# ccr_v10.net
KiCad netlist of a schematic drawn in EAGLE
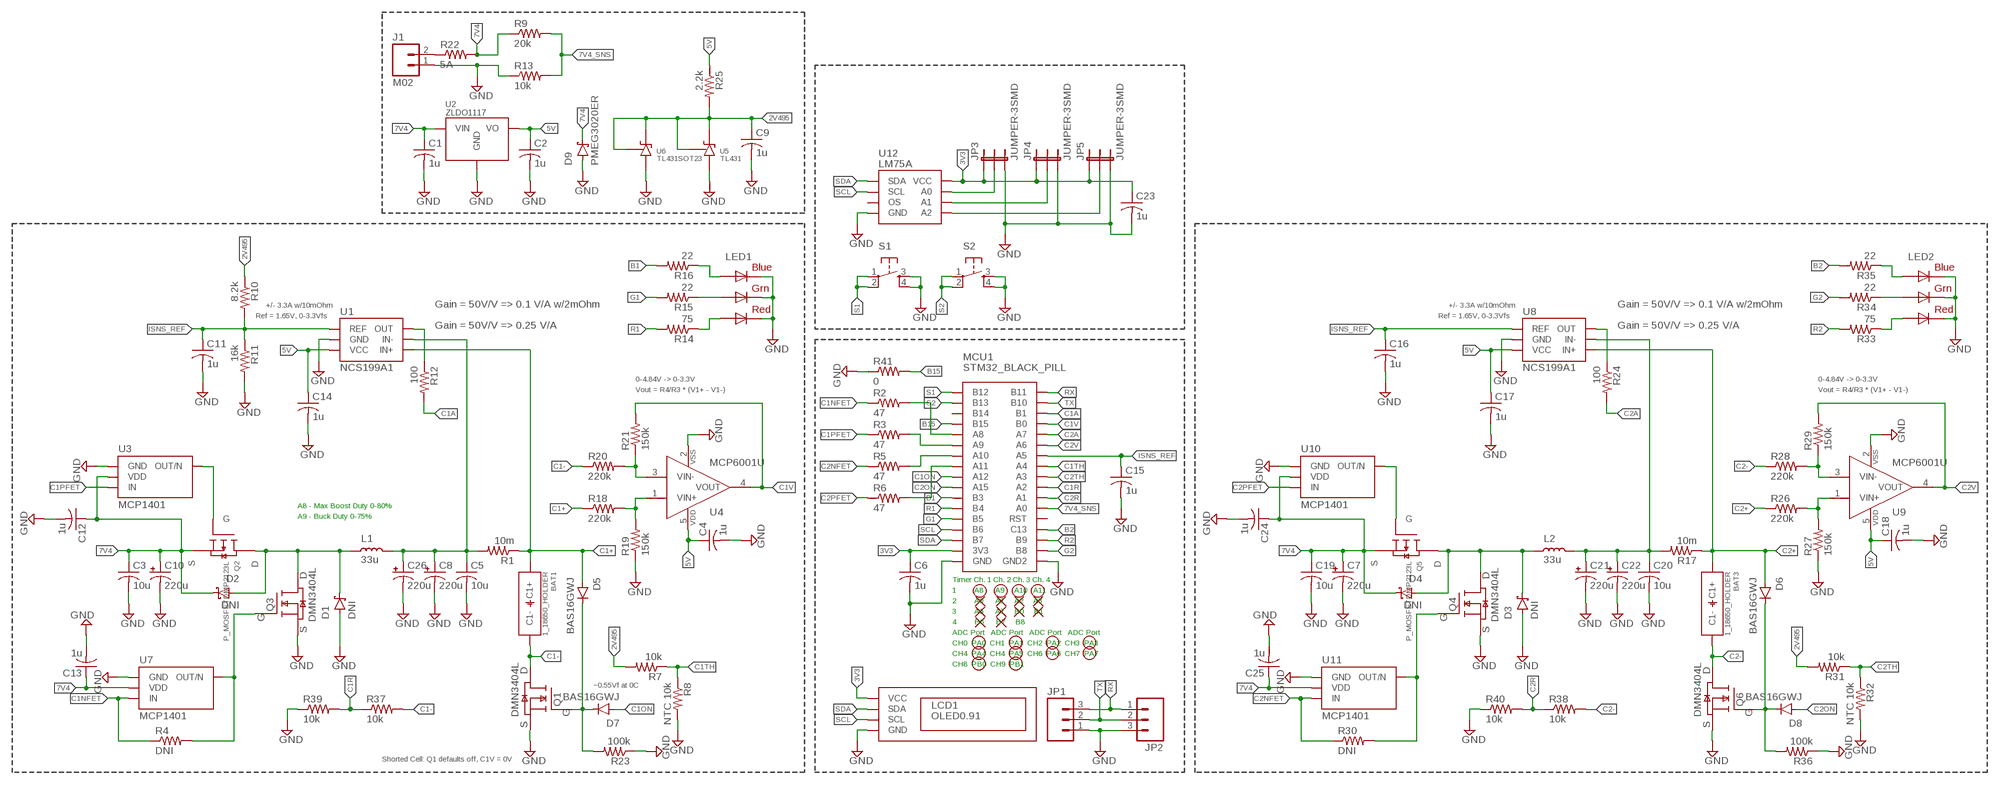
[diagram p0: schematic, sheet 1]

(export (version "E")
  (design (tool "Eeschema 10.0.6"))
  (components
    (comp (ref "BAT1")
      (value "1_18650_HOLDER")
      (footprint "eagle-import:1S_18650_SMD_NH")
      (libsource (lib "eagle-import") (part "1_18650_HOLDER"))
    )
    (comp (ref "BAT3")
      (value "1_18650_HOLDER")
      (footprint "eagle-import:1S_18650_SMD_NH")
      (libsource (lib "eagle-import") (part "1_18650_HOLDER"))
    )
    (comp (ref "C1")
      (value "1u")
      (footprint "eagle-import:C0402")
      (libsource (lib "eagle-import") (part "C-USC0402"))
    )
    (comp (ref "C2")
      (value "1u")
      (footprint "eagle-import:C0402")
      (libsource (lib "eagle-import") (part "C-USC0402"))
    )
    (comp (ref "C3")
      (value "10u")
      (footprint "eagle-import:C1206")
      (libsource (lib "eagle-import") (part "C-USC1206"))
    )
    (comp (ref "C4")
      (value "1u")
      (footprint "eagle-import:C0402")
      (libsource (lib "eagle-import") (part "C-USC0402"))
    )
    (comp (ref "C5")
      (value "10u")
      (footprint "eagle-import:C1206")
      (libsource (lib "eagle-import") (part "C-USC1206"))
    )
    (comp (ref "C6")
      (value "1u")
      (footprint "eagle-import:C0402")
      (libsource (lib "eagle-import") (part "C-USC0402"))
    )
    (comp (ref "C7")
      (value "220u")
      (footprint "eagle-import:PANASONIC_D")
      (libsource (lib "eagle-import") (part "CPOL-USD"))
    )
    (comp (ref "C8")
      (value "220u")
      (footprint "eagle-import:PANASONIC_D")
      (libsource (lib "eagle-import") (part "CPOL-USD"))
    )
    (comp (ref "C9")
      (value "1u")
      (footprint "eagle-import:C0402")
      (libsource (lib "eagle-import") (part "C-USC0402"))
    )
    (comp (ref "C10")
      (value "220u")
      (footprint "eagle-import:PANASONIC_D")
      (libsource (lib "eagle-import") (part "CPOL-USD"))
    )
    (comp (ref "C11")
      (value "1u")
      (footprint "eagle-import:C0402")
      (libsource (lib "eagle-import") (part "C-USC0402"))
    )
    (comp (ref "C12")
      (value "1u")
      (footprint "eagle-import:C0402")
      (libsource (lib "eagle-import") (part "C-USC0402"))
    )
    (comp (ref "C13")
      (value "1u")
      (footprint "eagle-import:C0402")
      (libsource (lib "eagle-import") (part "C-USC0402"))
    )
    (comp (ref "C14")
      (value "1u")
      (footprint "eagle-import:C0402")
      (libsource (lib "eagle-import") (part "C-USC0402"))
    )
    (comp (ref "C15")
      (value "1u")
      (footprint "eagle-import:C0402")
      (libsource (lib "eagle-import") (part "C-USC0402"))
    )
    (comp (ref "C16")
      (value "1u")
      (footprint "eagle-import:C0402")
      (libsource (lib "eagle-import") (part "C-USC0402"))
    )
    (comp (ref "C17")
      (value "1u")
      (footprint "eagle-import:C0402")
      (libsource (lib "eagle-import") (part "C-USC0402"))
    )
    (comp (ref "C18")
      (value "1u")
      (footprint "eagle-import:C0402")
      (libsource (lib "eagle-import") (part "C-USC0402"))
    )
    (comp (ref "C19")
      (value "10u")
      (footprint "eagle-import:C1206")
      (libsource (lib "eagle-import") (part "C-USC1206"))
    )
    (comp (ref "C20")
      (value "10u")
      (footprint "eagle-import:C1206")
      (libsource (lib "eagle-import") (part "C-USC1206"))
    )
    (comp (ref "C21")
      (value "220u")
      (footprint "eagle-import:PANASONIC_D")
      (libsource (lib "eagle-import") (part "CPOL-USD"))
    )
    (comp (ref "C22")
      (value "220u")
      (footprint "eagle-import:PANASONIC_D")
      (libsource (lib "eagle-import") (part "CPOL-USD"))
    )
    (comp (ref "C23")
      (value "1u")
      (footprint "eagle-import:C0402")
      (libsource (lib "eagle-import") (part "C-USC0402"))
    )
    (comp (ref "C24")
      (value "1u")
      (footprint "eagle-import:C0402")
      (libsource (lib "eagle-import") (part "C-USC0402"))
    )
    (comp (ref "C25")
      (value "1u")
      (footprint "eagle-import:C0402")
      (libsource (lib "eagle-import") (part "C-USC0402"))
    )
    (comp (ref "C26")
      (value "220u")
      (footprint "eagle-import:PANASONIC_D")
      (libsource (lib "eagle-import") (part "CPOL-USD"))
    )
    (comp (ref "D1")
      (value "DNI")
      (footprint "eagle-import:SOD123W")
      (libsource (lib "eagle-import") (part "PMEG3020ER"))
    )
    (comp (ref "D2")
      (value "DNI")
      (footprint "eagle-import:SOD123W")
      (libsource (lib "eagle-import") (part "PMEG3020ER"))
    )
    (comp (ref "D3")
      (value "DNI")
      (footprint "eagle-import:SOD123W")
      (libsource (lib "eagle-import") (part "PMEG3020ER"))
    )
    (comp (ref "D4")
      (value "DNI")
      (footprint "eagle-import:SOD123W")
      (libsource (lib "eagle-import") (part "PMEG3020ER"))
    )
    (comp (ref "D5")
      (value "BAS16GWJ")
      (footprint "eagle-import:SOD323")
      (libsource (lib "eagle-import") (part "BAT60A"))
    )
    (comp (ref "D6")
      (value "BAS16GWJ")
      (footprint "eagle-import:SOD323")
      (libsource (lib "eagle-import") (part "BAT60A"))
    )
    (comp (ref "D7")
      (value "BAS16GWJ")
      (footprint "eagle-import:SOD323")
      (libsource (lib "eagle-import") (part "BAT60A"))
    )
    (comp (ref "D8")
      (value "BAS16GWJ")
      (footprint "eagle-import:SOD323")
      (libsource (lib "eagle-import") (part "BAT60A"))
    )
    (comp (ref "D9")
      (value "PMEG3020ER")
      (footprint "eagle-import:SOD123W")
      (libsource (lib "eagle-import") (part "PMEG3020ER"))
    )
    (comp (ref "J1")
      (value "M02")
      (footprint "eagle-import:PHOENIXCONTACT1935161")
      (libsource (lib "eagle-import") (part "M02"))
    )
    (comp (ref "JP1")
      (value "M03PTH")
      (footprint "eagle-import:1X03")
      (libsource (lib "eagle-import") (part "M03PTH"))
    )
    (comp (ref "JP2")
      (value "M03PTH")
      (footprint "eagle-import:1X03")
      (libsource (lib "eagle-import") (part "M03PTH"))
    )
    (comp (ref "JP3")
      (value "JUMPER-3SMD")
      (footprint "eagle-import:SJ_3")
      (libsource (lib "eagle-import") (part "JUMPER-3SMD"))
    )
    (comp (ref "JP4")
      (value "JUMPER-3SMD")
      (footprint "eagle-import:SJ_3")
      (libsource (lib "eagle-import") (part "JUMPER-3SMD"))
    )
    (comp (ref "JP5")
      (value "JUMPER-3SMD")
      (footprint "eagle-import:SJ_3")
      (libsource (lib "eagle-import") (part "JUMPER-3SMD"))
    )
    (comp (ref "L1")
      (value "33u")
      (footprint "eagle-import:INDUCTOR_SMD_13MM")
      (libsource (lib "eagle-import") (part "SDR1307"))
    )
    (comp (ref "L2")
      (value "33u")
      (footprint "eagle-import:INDUCTOR_SMD_13MM")
      (libsource (lib "eagle-import") (part "SDR1307"))
    )
    (comp (ref "LCD1")
      (value "OLED0.91")
      (footprint "eagle-import:OLED0.91")
      (libsource (lib "eagle-import") (part "OLED0.91"))
    )
    (comp (ref "LED1")
      (value "RGBLED5050")
      (footprint "eagle-import:RGBLED5050")
      (libsource (lib "eagle-import") (part "RGBLED5050"))
    )
    (comp (ref "LED2")
      (value "RGBLED5050")
      (footprint "eagle-import:RGBLED5050")
      (libsource (lib "eagle-import") (part "RGBLED5050"))
    )
    (comp (ref "MCU1")
      (value "STM32_BLACK_PILL")
      (footprint "eagle-import:STM32_BLACK_PILL_BOT")
      (libsource (lib "eagle-import") (part "STM32_BLACK_PILL"))
    )
    (comp (ref "Q1")
      (value "DMN3404L")
      (footprint "eagle-import:SOT23")
      (libsource (lib "eagle-import") (part "DMN3404L"))
    )
    (comp (ref "Q2")
      (value "P_MOSFETDMP2123L")
      (footprint "eagle-import:SOT23")
      (libsource (lib "eagle-import") (part "P_MOSFETDMP2123L"))
    )
    (comp (ref "Q3")
      (value "DMN3404L")
      (footprint "eagle-import:SOT23")
      (libsource (lib "eagle-import") (part "DMN3404L"))
    )
    (comp (ref "Q4")
      (value "DMN3404L")
      (footprint "eagle-import:SOT23")
      (libsource (lib "eagle-import") (part "DMN3404L"))
    )
    (comp (ref "Q5")
      (value "P_MOSFETDMP2123L")
      (footprint "eagle-import:SOT23")
      (libsource (lib "eagle-import") (part "P_MOSFETDMP2123L"))
    )
    (comp (ref "Q6")
      (value "DMN3404L")
      (footprint "eagle-import:SOT23")
      (libsource (lib "eagle-import") (part "DMN3404L"))
    )
    (comp (ref "R1")
      (value "10m")
      (footprint "eagle-import:R2512")
      (libsource (lib "eagle-import") (part "R-US_R2512"))
    )
    (comp (ref "R2")
      (value "47")
      (footprint "eagle-import:R0402")
      (libsource (lib "eagle-import") (part "R-US_R0402"))
    )
    (comp (ref "R3")
      (value "47")
      (footprint "eagle-import:R0402")
      (libsource (lib "eagle-import") (part "R-US_R0402"))
    )
    (comp (ref "R4")
      (value "DNI")
      (footprint "eagle-import:R0402")
      (libsource (lib "eagle-import") (part "R-US_R0402"))
    )
    (comp (ref "R5")
      (value "47")
      (footprint "eagle-import:R0402")
      (libsource (lib "eagle-import") (part "R-US_R0402"))
    )
    (comp (ref "R6")
      (value "47")
      (footprint "eagle-import:R0402")
      (libsource (lib "eagle-import") (part "R-US_R0402"))
    )
    (comp (ref "R7")
      (value "10k")
      (footprint "eagle-import:R0402")
      (libsource (lib "eagle-import") (part "R-US_R0402"))
    )
    (comp (ref "R8")
      (value "NTC 10k")
      (footprint "eagle-import:R0402")
      (libsource (lib "eagle-import") (part "R-US_R0402"))
    )
    (comp (ref "R9")
      (value "20k")
      (footprint "eagle-import:R0402")
      (libsource (lib "eagle-import") (part "R-US_R0402"))
    )
    (comp (ref "R10")
      (value "8.2k")
      (footprint "eagle-import:R0402")
      (libsource (lib "eagle-import") (part "R-US_R0402"))
    )
    (comp (ref "R11")
      (value "16k")
      (footprint "eagle-import:R0402")
      (libsource (lib "eagle-import") (part "R-US_R0402"))
    )
    (comp (ref "R12")
      (value "100")
      (footprint "eagle-import:R0402")
      (libsource (lib "eagle-import") (part "R-US_R0402"))
    )
    (comp (ref "R13")
      (value "10k")
      (footprint "eagle-import:R0402")
      (libsource (lib "eagle-import") (part "R-US_R0402"))
    )
    (comp (ref "R14")
      (value "75")
      (footprint "eagle-import:R0402")
      (libsource (lib "eagle-import") (part "R-US_R0402"))
    )
    (comp (ref "R15")
      (value "22")
      (footprint "eagle-import:R0402")
      (libsource (lib "eagle-import") (part "R-US_R0402"))
    )
    (comp (ref "R16")
      (value "22")
      (footprint "eagle-import:R0402")
      (libsource (lib "eagle-import") (part "R-US_R0402"))
    )
    (comp (ref "R17")
      (value "10m")
      (footprint "eagle-import:R2512")
      (libsource (lib "eagle-import") (part "R-US_R2512"))
    )
    (comp (ref "R18")
      (value "220k")
      (footprint "eagle-import:R0402")
      (libsource (lib "eagle-import") (part "R-US_R0402"))
    )
    (comp (ref "R19")
      (value "150k")
      (footprint "eagle-import:R0402")
      (libsource (lib "eagle-import") (part "R-US_R0402"))
    )
    (comp (ref "R20")
      (value "220k")
      (footprint "eagle-import:R0402")
      (libsource (lib "eagle-import") (part "R-US_R0402"))
    )
    (comp (ref "R21")
      (value "150k")
      (footprint "eagle-import:R0402")
      (libsource (lib "eagle-import") (part "R-US_R0402"))
    )
    (comp (ref "R22")
      (value "5A")
      (footprint "eagle-import:R1206")
      (libsource (lib "eagle-import") (part "R-US_R1206"))
    )
    (comp (ref "R23")
      (value "100k")
      (footprint "eagle-import:R0402")
      (libsource (lib "eagle-import") (part "R-US_R0402"))
    )
    (comp (ref "R24")
      (value "100")
      (footprint "eagle-import:R0402")
      (libsource (lib "eagle-import") (part "R-US_R0402"))
    )
    (comp (ref "R25")
      (value "2.2k")
      (footprint "eagle-import:R0402")
      (libsource (lib "eagle-import") (part "R-US_R0402"))
    )
    (comp (ref "R26")
      (value "220k")
      (footprint "eagle-import:R0402")
      (libsource (lib "eagle-import") (part "R-US_R0402"))
    )
    (comp (ref "R27")
      (value "150k")
      (footprint "eagle-import:R0402")
      (libsource (lib "eagle-import") (part "R-US_R0402"))
    )
    (comp (ref "R28")
      (value "220k")
      (footprint "eagle-import:R0402")
      (libsource (lib "eagle-import") (part "R-US_R0402"))
    )
    (comp (ref "R29")
      (value "150k")
      (footprint "eagle-import:R0402")
      (libsource (lib "eagle-import") (part "R-US_R0402"))
    )
    (comp (ref "R30")
      (value "DNI")
      (footprint "eagle-import:R0402")
      (libsource (lib "eagle-import") (part "R-US_R0402"))
    )
    (comp (ref "R31")
      (value "10k")
      (footprint "eagle-import:R0402")
      (libsource (lib "eagle-import") (part "R-US_R0402"))
    )
    (comp (ref "R32")
      (value "NTC 10k")
      (footprint "eagle-import:R0402")
      (libsource (lib "eagle-import") (part "R-US_R0402"))
    )
    (comp (ref "R33")
      (value "75")
      (footprint "eagle-import:R0402")
      (libsource (lib "eagle-import") (part "R-US_R0402"))
    )
    (comp (ref "R34")
      (value "22")
      (footprint "eagle-import:R0402")
      (libsource (lib "eagle-import") (part "R-US_R0402"))
    )
    (comp (ref "R35")
      (value "22")
      (footprint "eagle-import:R0402")
      (libsource (lib "eagle-import") (part "R-US_R0402"))
    )
    (comp (ref "R36")
      (value "100k")
      (footprint "eagle-import:R0402")
      (libsource (lib "eagle-import") (part "R-US_R0402"))
    )
    (comp (ref "R37")
      (value "10k")
      (footprint "eagle-import:R0402")
      (libsource (lib "eagle-import") (part "R-US_R0402"))
    )
    (comp (ref "R38")
      (value "10k")
      (footprint "eagle-import:R0402")
      (libsource (lib "eagle-import") (part "R-US_R0402"))
    )
    (comp (ref "R39")
      (value "10k")
      (footprint "eagle-import:R0402")
      (libsource (lib "eagle-import") (part "R-US_R0402"))
    )
    (comp (ref "R40")
      (value "10k")
      (footprint "eagle-import:R0402")
      (libsource (lib "eagle-import") (part "R-US_R0402"))
    )
    (comp (ref "R41")
      (value "0")
      (footprint "eagle-import:R0402")
      (libsource (lib "eagle-import") (part "R-US_R0402"))
    )
    (comp (ref "S1")
      (value "TAC_SWITCHSMD")
      (footprint "eagle-import:TACTILE_SWITCH_SMD")
      (libsource (lib "eagle-import") (part "TAC_SWITCHSMD"))
    )
    (comp (ref "S2")
      (value "TAC_SWITCHSMD")
      (footprint "eagle-import:TACTILE_SWITCH_SMD")
      (libsource (lib "eagle-import") (part "TAC_SWITCHSMD"))
    )
    (comp (ref "U1")
      (value "NCS199A1")
      (footprint "eagle-import:SOT-363")
      (libsource (lib "eagle-import") (part "INA214"))
    )
    (comp (ref "U2")
      (value "ZLDO1117")
      (footprint "eagle-import:TO-261")
      (libsource (lib "eagle-import") (part "ZLDO1117"))
    )
    (comp (ref "U3")
      (value "MCP1401")
      (footprint "eagle-import:SOT23-5")
      (libsource (lib "eagle-import") (part "MCP1401"))
    )
    (comp (ref "U4")
      (value "MCP6001U")
      (footprint "eagle-import:SOT23-5")
      (libsource (lib "eagle-import") (part "MCP6001U"))
    )
    (comp (ref "U5")
      (value "TL431")
      (footprint "eagle-import:SOT23-5")
      (libsource (lib "eagle-import") (part "TL431"))
    )
    (comp (ref "U6")
      (value "TL431SOT23")
      (footprint "eagle-import:SOT23")
      (libsource (lib "eagle-import") (part "TL431SOT23"))
    )
    (comp (ref "U7")
      (value "MCP1401")
      (footprint "eagle-import:SOT23-5")
      (libsource (lib "eagle-import") (part "MCP1401"))
    )
    (comp (ref "U8")
      (value "NCS199A1")
      (footprint "eagle-import:SOT-363")
      (libsource (lib "eagle-import") (part "INA214"))
    )
    (comp (ref "U9")
      (value "MCP6001U")
      (footprint "eagle-import:SOT23-5")
      (libsource (lib "eagle-import") (part "MCP6001U"))
    )
    (comp (ref "U10")
      (value "MCP1401")
      (footprint "eagle-import:SOT23-5")
      (libsource (lib "eagle-import") (part "MCP1401"))
    )
    (comp (ref "U11")
      (value "MCP1401")
      (footprint "eagle-import:SOT23-5")
      (libsource (lib "eagle-import") (part "MCP1401"))
    )
    (comp (ref "U12")
      (value "LM75A")
      (footprint "eagle-import:8-SOIC")
      (libsource (lib "eagle-import") (part "LM75A"))
    )
  )
  (nets
    (net (code "1") (name "2V495") (class "Default")
      (node (ref "C9") (pin "1") (pinfunction "1_1") (pintype "passive"))
      (node (ref "R10") (pin "1") (pinfunction "1_1") (pintype "passive"))
      (node (ref "R25") (pin "2") (pinfunction "2_2") (pintype "passive"))
      (node (ref "R31") (pin "2") (pinfunction "2_2") (pintype "passive"))
      (node (ref "R7") (pin "2") (pinfunction "2_2") (pintype "passive"))
      (node (ref "U5") (pin "3") (pinfunction "K_3") (pintype "passive"))
      (node (ref "U5") (pin "4") (pinfunction "REF_4") (pintype "passive"))
      (node (ref "U6") (pin "1") (pinfunction "K_1") (pintype "passive"))
      (node (ref "U6") (pin "2") (pinfunction "REF_2") (pintype "passive"))
    )
    (net (code "2") (name "3V3") (class "Default")
      (node (ref "C23") (pin "1") (pinfunction "1_1") (pintype "passive"))
      (node (ref "C6") (pin "1") (pinfunction "1_1") (pintype "passive"))
      (node (ref "JP3") (pin "1") (pinfunction "1_1") (pintype "passive"))
      (node (ref "JP4") (pin "1") (pinfunction "1_1") (pintype "passive"))
      (node (ref "JP5") (pin "1") (pinfunction "1_1") (pintype "passive"))
      (node (ref "LCD1") (pin "2-VCC") (pinfunction "VCC_2-VCC") (pintype "bidirectional"))
      (node (ref "MCU1") (pin "3V3") (pinfunction "3V3_3V3") (pintype "bidirectional"))
      (node (ref "U12") (pin "8") (pinfunction "VCC_8") (pintype "bidirectional"))
    )
    (net (code "3") (name "5V") (class "Default")
      (node (ref "C14") (pin "1") (pinfunction "1_1") (pintype "passive"))
      (node (ref "C17") (pin "1") (pinfunction "1_1") (pintype "passive"))
      (node (ref "C18") (pin "1") (pinfunction "1_1") (pintype "passive"))
      (node (ref "C2") (pin "1") (pinfunction "1_1") (pintype "passive"))
      (node (ref "C4") (pin "1") (pinfunction "1_1") (pintype "passive"))
      (node (ref "R25") (pin "1") (pinfunction "1_1") (pintype "passive"))
      (node (ref "U1") (pin "3") (pinfunction "VCC_3") (pintype "bidirectional"))
      (node (ref "U2") (pin "2") (pinfunction "VO_2") (pintype "bidirectional"))
      (node (ref "U2") (pin "4") (pinfunction "VO_4") (pintype "bidirectional"))
      (node (ref "U4") (pin "5") (pinfunction "VDD_5") (pintype "bidirectional"))
      (node (ref "U8") (pin "3") (pinfunction "VCC_3") (pintype "bidirectional"))
      (node (ref "U9") (pin "5") (pinfunction "VDD_5") (pintype "bidirectional"))
    )
    (net (code "4") (name "7V4") (class "Default")
      (node (ref "C1") (pin "1") (pinfunction "1_1") (pintype "passive"))
      (node (ref "C10") (pin "+") (pinfunction "+_+") (pintype "passive"))
      (node (ref "C12") (pin "1") (pinfunction "1_1") (pintype "passive"))
      (node (ref "C13") (pin "1") (pinfunction "1_1") (pintype "passive"))
      (node (ref "C19") (pin "1") (pinfunction "1_1") (pintype "passive"))
      (node (ref "C24") (pin "1") (pinfunction "1_1") (pintype "passive"))
      (node (ref "C25") (pin "1") (pinfunction "1_1") (pintype "passive"))
      (node (ref "C3") (pin "1") (pinfunction "1_1") (pintype "passive"))
      (node (ref "C7") (pin "+") (pinfunction "+_+") (pintype "passive"))
      (node (ref "D2") (pin "K") (pinfunction "CATHODE_K") (pintype "passive"))
      (node (ref "D4") (pin "K") (pinfunction "CATHODE_K") (pintype "passive"))
      (node (ref "D9") (pin "K") (pinfunction "CATHODE_K") (pintype "passive"))
      (node (ref "Q2") (pin "2") (pinfunction "S_2") (pintype "bidirectional"))
      (node (ref "Q5") (pin "2") (pinfunction "S_2") (pintype "bidirectional"))
      (node (ref "R22") (pin "2") (pinfunction "2_2") (pintype "passive"))
      (node (ref "R9") (pin "1") (pinfunction "1_1") (pintype "passive"))
      (node (ref "U10") (pin "2") (pinfunction "VDD_2") (pintype "bidirectional"))
      (node (ref "U11") (pin "2") (pinfunction "VDD_2") (pintype "bidirectional"))
      (node (ref "U2") (pin "3") (pinfunction "VIN_3") (pintype "bidirectional"))
      (node (ref "U3") (pin "2") (pinfunction "VDD_2") (pintype "bidirectional"))
      (node (ref "U7") (pin "2") (pinfunction "VDD_2") (pintype "bidirectional"))
    )
    (net (code "5") (name "7V4_SNS") (class "Default")
      (node (ref "MCU1") (pin "A0") (pinfunction "A0_A0") (pintype "bidirectional"))
      (node (ref "R13") (pin "2") (pinfunction "2_2") (pintype "passive"))
      (node (ref "R9") (pin "2") (pinfunction "2_2") (pintype "passive"))
    )
    (net (code "6") (name "B1") (class "Default")
      (node (ref "MCU1") (pin "B3") (pinfunction "B3_B3") (pintype "bidirectional"))
      (node (ref "R16") (pin "2") (pinfunction "2_2") (pintype "passive"))
    )
    (net (code "7") (name "B2") (class "Default")
      (node (ref "MCU1") (pin "C13") (pinfunction "C13_C13") (pintype "bidirectional"))
      (node (ref "R35") (pin "2") (pinfunction "2_2") (pintype "passive"))
    )
    (net (code "8") (name "B15") (class "Default")
      (node (ref "MCU1") (pin "B15") (pinfunction "B15_B15") (pintype "bidirectional"))
      (node (ref "R41") (pin "2") (pinfunction "2_2") (pintype "passive"))
    )
    (net (code "9") (name "C1+") (class "Default")
      (node (ref "BAT1") (pin "1+") (pinfunction "C1+_1+") (pintype "bidirectional"))
      (node (ref "D5") (pin "A") (pinfunction "ANODE_A") (pintype "passive"))
      (node (ref "R1") (pin "1") (pinfunction "1_1") (pintype "passive"))
      (node (ref "R18") (pin "1") (pinfunction "1_1") (pintype "passive"))
      (node (ref "U1") (pin "4") (pinfunction "IN+_4") (pintype "bidirectional"))
    )
    (net (code "10") (name "C1-") (class "Default")
      (node (ref "BAT1") (pin "1-") (pinfunction "C1-_1-") (pintype "bidirectional"))
      (node (ref "Q1") (pin "3") (pinfunction "D_3") (pintype "passive"))
      (node (ref "R20") (pin "1") (pinfunction "1_1") (pintype "passive"))
      (node (ref "R37") (pin "2") (pinfunction "2_2") (pintype "passive"))
    )
    (net (code "11") (name "C1A") (class "Default")
      (node (ref "MCU1") (pin "B1") (pinfunction "B1_B1") (pintype "bidirectional"))
      (node (ref "R12") (pin "2") (pinfunction "2_2") (pintype "passive"))
    )
    (net (code "12") (name "C1NFET") (class "Default")
      (node (ref "R2") (pin "1") (pinfunction "1_1") (pintype "passive"))
      (node (ref "R4") (pin "1") (pinfunction "1_1") (pintype "passive"))
      (node (ref "U7") (pin "3") (pinfunction "IN_3") (pintype "bidirectional"))
    )
    (net (code "13") (name "C1ON") (class "Default")
      (node (ref "D7") (pin "A") (pinfunction "ANODE_A") (pintype "passive"))
      (node (ref "MCU1") (pin "A12") (pinfunction "A12_A12") (pintype "bidirectional"))
    )
    (net (code "14") (name "C1PFET") (class "Default")
      (node (ref "R3") (pin "1") (pinfunction "1_1") (pintype "passive"))
      (node (ref "U3") (pin "3") (pinfunction "IN_3") (pintype "bidirectional"))
    )
    (net (code "15") (name "C1R") (class "Default")
      (node (ref "MCU1") (pin "A2") (pinfunction "A2_A2") (pintype "bidirectional"))
      (node (ref "R37") (pin "1") (pinfunction "1_1") (pintype "passive"))
      (node (ref "R39") (pin "2") (pinfunction "2_2") (pintype "passive"))
    )
    (net (code "16") (name "C1TH") (class "Default")
      (node (ref "MCU1") (pin "A4") (pinfunction "A4_A4") (pintype "bidirectional"))
      (node (ref "R7") (pin "1") (pinfunction "1_1") (pintype "passive"))
      (node (ref "R8") (pin "1") (pinfunction "1_1") (pintype "passive"))
    )
    (net (code "17") (name "C1V") (class "Default")
      (node (ref "MCU1") (pin "B0") (pinfunction "B0_B0") (pintype "bidirectional"))
      (node (ref "R21") (pin "2") (pinfunction "2_2") (pintype "passive"))
      (node (ref "U4") (pin "4") (pinfunction "VOUT_4") (pintype "bidirectional"))
    )
    (net (code "18") (name "C2+") (class "Default")
      (node (ref "BAT3") (pin "1+") (pinfunction "C1+_1+") (pintype "bidirectional"))
      (node (ref "D6") (pin "A") (pinfunction "ANODE_A") (pintype "passive"))
      (node (ref "R17") (pin "1") (pinfunction "1_1") (pintype "passive"))
      (node (ref "R26") (pin "1") (pinfunction "1_1") (pintype "passive"))
      (node (ref "U8") (pin "4") (pinfunction "IN+_4") (pintype "bidirectional"))
    )
    (net (code "19") (name "C2-") (class "Default")
      (node (ref "BAT3") (pin "1-") (pinfunction "C1-_1-") (pintype "bidirectional"))
      (node (ref "Q6") (pin "3") (pinfunction "D_3") (pintype "passive"))
      (node (ref "R28") (pin "1") (pinfunction "1_1") (pintype "passive"))
      (node (ref "R38") (pin "2") (pinfunction "2_2") (pintype "passive"))
    )
    (net (code "20") (name "C2A") (class "Default")
      (node (ref "MCU1") (pin "A7") (pinfunction "A7_A7") (pintype "bidirectional"))
      (node (ref "R24") (pin "2") (pinfunction "2_2") (pintype "passive"))
    )
    (net (code "21") (name "C2NFET") (class "Default")
      (node (ref "R30") (pin "1") (pinfunction "1_1") (pintype "passive"))
      (node (ref "R5") (pin "1") (pinfunction "1_1") (pintype "passive"))
      (node (ref "U11") (pin "3") (pinfunction "IN_3") (pintype "bidirectional"))
    )
    (net (code "22") (name "C2ON") (class "Default")
      (node (ref "D8") (pin "A") (pinfunction "ANODE_A") (pintype "passive"))
      (node (ref "MCU1") (pin "A15") (pinfunction "A15_A15") (pintype "bidirectional"))
    )
    (net (code "23") (name "C2PFET") (class "Default")
      (node (ref "R6") (pin "1") (pinfunction "1_1") (pintype "passive"))
      (node (ref "U10") (pin "3") (pinfunction "IN_3") (pintype "bidirectional"))
    )
    (net (code "24") (name "C2R") (class "Default")
      (node (ref "MCU1") (pin "A1") (pinfunction "A1_A1") (pintype "bidirectional"))
      (node (ref "R38") (pin "1") (pinfunction "1_1") (pintype "passive"))
      (node (ref "R40") (pin "2") (pinfunction "2_2") (pintype "passive"))
    )
    (net (code "25") (name "C2TH") (class "Default")
      (node (ref "MCU1") (pin "A3") (pinfunction "A3_A3") (pintype "bidirectional"))
      (node (ref "R31") (pin "1") (pinfunction "1_1") (pintype "passive"))
      (node (ref "R32") (pin "1") (pinfunction "1_1") (pintype "passive"))
    )
    (net (code "26") (name "C2V") (class "Default")
      (node (ref "MCU1") (pin "A6") (pinfunction "A6_A6") (pintype "bidirectional"))
      (node (ref "R29") (pin "2") (pinfunction "2_2") (pintype "passive"))
      (node (ref "U9") (pin "4") (pinfunction "VOUT_4") (pintype "bidirectional"))
    )
    (net (code "27") (name "G1") (class "Default")
      (node (ref "MCU1") (pin "B5") (pinfunction "B5_B5") (pintype "bidirectional"))
      (node (ref "R15") (pin "2") (pinfunction "2_2") (pintype "passive"))
    )
    (net (code "28") (name "G2") (class "Default")
      (node (ref "MCU1") (pin "B8") (pinfunction "B8_B8") (pintype "bidirectional"))
      (node (ref "R34") (pin "2") (pinfunction "2_2") (pintype "passive"))
    )
    (net (code "29") (name "GND") (class "Default")
      (node (ref "C1") (pin "2") (pinfunction "2_2") (pintype "passive"))
      (node (ref "C10") (pin "-") (pinfunction "-_-") (pintype "passive"))
      (node (ref "C11") (pin "2") (pinfunction "2_2") (pintype "passive"))
      (node (ref "C12") (pin "2") (pinfunction "2_2") (pintype "passive"))
      (node (ref "C13") (pin "2") (pinfunction "2_2") (pintype "passive"))
      (node (ref "C14") (pin "2") (pinfunction "2_2") (pintype "passive"))
      (node (ref "C15") (pin "2") (pinfunction "2_2") (pintype "passive"))
      (node (ref "C16") (pin "2") (pinfunction "2_2") (pintype "passive"))
      (node (ref "C17") (pin "2") (pinfunction "2_2") (pintype "passive"))
      (node (ref "C18") (pin "2") (pinfunction "2_2") (pintype "passive"))
      (node (ref "C19") (pin "2") (pinfunction "2_2") (pintype "passive"))
      (node (ref "C2") (pin "2") (pinfunction "2_2") (pintype "passive"))
      (node (ref "C20") (pin "2") (pinfunction "2_2") (pintype "passive"))
      (node (ref "C21") (pin "-") (pinfunction "-_-") (pintype "passive"))
      (node (ref "C22") (pin "-") (pinfunction "-_-") (pintype "passive"))
      (node (ref "C23") (pin "2") (pinfunction "2_2") (pintype "passive"))
      (node (ref "C24") (pin "2") (pinfunction "2_2") (pintype "passive"))
      (node (ref "C25") (pin "2") (pinfunction "2_2") (pintype "passive"))
      (node (ref "C26") (pin "-") (pinfunction "-_-") (pintype "passive"))
      (node (ref "C3") (pin "2") (pinfunction "2_2") (pintype "passive"))
      (node (ref "C4") (pin "2") (pinfunction "2_2") (pintype "passive"))
      (node (ref "C5") (pin "2") (pinfunction "2_2") (pintype "passive"))
      (node (ref "C6") (pin "2") (pinfunction "2_2") (pintype "passive"))
      (node (ref "C7") (pin "-") (pinfunction "-_-") (pintype "passive"))
      (node (ref "C8") (pin "-") (pinfunction "-_-") (pintype "passive"))
      (node (ref "C9") (pin "2") (pinfunction "2_2") (pintype "passive"))
      (node (ref "D1") (pin "A") (pinfunction "ANODE_A") (pintype "passive"))
      (node (ref "D3") (pin "A") (pinfunction "ANODE_A") (pintype "passive"))
      (node (ref "D9") (pin "A") (pinfunction "ANODE_A") (pintype "passive"))
      (node (ref "J1") (pin "1") (pinfunction "1_1") (pintype "passive"))
      (node (ref "JP1") (pin "1") (pinfunction "1_1") (pintype "passive"))
      (node (ref "JP2") (pin "3") (pinfunction "3_3") (pintype "passive"))
      (node (ref "JP3") (pin "3") (pinfunction "3_3") (pintype "passive"))
      (node (ref "JP4") (pin "3") (pinfunction "3_3") (pintype "passive"))
      (node (ref "JP5") (pin "3") (pinfunction "3_3") (pintype "passive"))
      (node (ref "LCD1") (pin "1=GND") (pinfunction "GND_1=GND") (pintype "bidirectional"))
      (node (ref "LED1") (pin "4") (pinfunction "BLUE_C_4") (pintype "bidirectional"))
      (node (ref "LED1") (pin "5") (pinfunction "RED_C_5") (pintype "bidirectional"))
      (node (ref "LED1") (pin "6") (pinfunction "GREEN_C_6") (pintype "bidirectional"))
      (node (ref "LED2") (pin "4") (pinfunction "BLUE_C_4") (pintype "bidirectional"))
      (node (ref "LED2") (pin "5") (pinfunction "RED_C_5") (pintype "bidirectional"))
      (node (ref "LED2") (pin "6") (pinfunction "GREEN_C_6") (pintype "bidirectional"))
      (node (ref "MCU1") (pin "GND1") (pinfunction "GND_GND1") (pintype "bidirectional"))
      (node (ref "MCU1") (pin "GND2") (pinfunction "GND2_GND2") (pintype "bidirectional"))
      (node (ref "Q1") (pin "2") (pinfunction "S_2") (pintype "passive"))
      (node (ref "Q3") (pin "2") (pinfunction "S_2") (pintype "passive"))
      (node (ref "Q4") (pin "2") (pinfunction "S_2") (pintype "passive"))
      (node (ref "Q6") (pin "2") (pinfunction "S_2") (pintype "passive"))
      (node (ref "R11") (pin "2") (pinfunction "2_2") (pintype "passive"))
      (node (ref "R13") (pin "1") (pinfunction "1_1") (pintype "passive"))
      (node (ref "R19") (pin "1") (pinfunction "1_1") (pintype "passive"))
      (node (ref "R23") (pin "1") (pinfunction "1_1") (pintype "passive"))
      (node (ref "R27") (pin "1") (pinfunction "1_1") (pintype "passive"))
      (node (ref "R32") (pin "2") (pinfunction "2_2") (pintype "passive"))
      (node (ref "R36") (pin "1") (pinfunction "1_1") (pintype "passive"))
      (node (ref "R39") (pin "1") (pinfunction "1_1") (pintype "passive"))
      (node (ref "R40") (pin "1") (pinfunction "1_1") (pintype "passive"))
      (node (ref "R41") (pin "1") (pinfunction "1_1") (pintype "passive"))
      (node (ref "R8") (pin "2") (pinfunction "2_2") (pintype "passive"))
      (node (ref "S1") (pin "3") (pinfunction "3_3") (pintype "passive"))
      (node (ref "S1") (pin "4") (pinfunction "4_4") (pintype "passive"))
      (node (ref "S2") (pin "3") (pinfunction "3_3") (pintype "passive"))
      (node (ref "S2") (pin "4") (pinfunction "4_4") (pintype "passive"))
      (node (ref "U1") (pin "2") (pinfunction "GND_2") (pintype "bidirectional"))
      (node (ref "U10") (pin "1") (pinfunction "GND_1") (pintype "bidirectional"))
      (node (ref "U10") (pin "4") (pinfunction "GND_4") (pintype "bidirectional"))
      (node (ref "U11") (pin "1") (pinfunction "GND_1") (pintype "bidirectional"))
      (node (ref "U11") (pin "4") (pinfunction "GND_4") (pintype "bidirectional"))
      (node (ref "U12") (pin "4") (pinfunction "GND_4") (pintype "bidirectional"))
      (node (ref "U2") (pin "1") (pinfunction "GND_1") (pintype "bidirectional"))
      (node (ref "U3") (pin "1") (pinfunction "GND_1") (pintype "bidirectional"))
      (node (ref "U3") (pin "4") (pinfunction "GND_4") (pintype "bidirectional"))
      (node (ref "U4") (pin "2") (pinfunction "VSS_2") (pintype "bidirectional"))
      (node (ref "U5") (pin "2") (pinfunction "A_2") (pintype "passive"))
      (node (ref "U5") (pin "5") (pinfunction "A_5") (pintype "passive"))
      (node (ref "U6") (pin "3") (pinfunction "A_3") (pintype "passive"))
      (node (ref "U7") (pin "1") (pinfunction "GND_1") (pintype "bidirectional"))
      (node (ref "U7") (pin "4") (pinfunction "GND_4") (pintype "bidirectional"))
      (node (ref "U8") (pin "2") (pinfunction "GND_2") (pintype "bidirectional"))
      (node (ref "U9") (pin "2") (pinfunction "VSS_2") (pintype "bidirectional"))
    )
    (net (code "30") (name "ISNS_REF") (class "Default")
      (node (ref "C11") (pin "1") (pinfunction "1_1") (pintype "passive"))
      (node (ref "C15") (pin "1") (pinfunction "1_1") (pintype "passive"))
      (node (ref "C16") (pin "1") (pinfunction "1_1") (pintype "passive"))
      (node (ref "MCU1") (pin "A5") (pinfunction "A5_A5") (pintype "bidirectional"))
      (node (ref "R10") (pin "2") (pinfunction "2_2") (pintype "passive"))
      (node (ref "R11") (pin "1") (pinfunction "1_1") (pintype "passive"))
      (node (ref "U1") (pin "1") (pinfunction "REF_1") (pintype "bidirectional"))
      (node (ref "U8") (pin "1") (pinfunction "REF_1") (pintype "bidirectional"))
    )
    (net (code "31") (name "Net-(D1-CATHODE)") (class "Default")
      (node (ref "D1") (pin "K") (pinfunction "CATHODE_K") (pintype "passive"))
      (node (ref "D2") (pin "A") (pinfunction "ANODE_A") (pintype "passive"))
      (node (ref "L1") (pin "1") (pinfunction "P$1_1") (pintype "passive"))
      (node (ref "Q2") (pin "3") (pinfunction "D_3") (pintype "bidirectional"))
      (node (ref "Q3") (pin "3") (pinfunction "D_3") (pintype "passive"))
    )
    (net (code "32") (name "Net-(D3-CATHODE)") (class "Default")
      (node (ref "D3") (pin "K") (pinfunction "CATHODE_K") (pintype "passive"))
      (node (ref "D4") (pin "A") (pinfunction "ANODE_A") (pintype "passive"))
      (node (ref "L2") (pin "1") (pinfunction "P$1_1") (pintype "passive"))
      (node (ref "Q4") (pin "3") (pinfunction "D_3") (pintype "passive"))
      (node (ref "Q5") (pin "3") (pinfunction "D_3") (pintype "bidirectional"))
    )
    (net (code "33") (name "Net-(D5-CATHODE)") (class "Default")
      (node (ref "D5") (pin "K") (pinfunction "CATHODE_K") (pintype "passive"))
      (node (ref "D7") (pin "K") (pinfunction "CATHODE_K") (pintype "passive"))
      (node (ref "Q1") (pin "1") (pinfunction "G_1") (pintype "input"))
      (node (ref "R23") (pin "2") (pinfunction "2_2") (pintype "passive"))
    )
    (net (code "34") (name "Net-(D6-CATHODE)") (class "Default")
      (node (ref "D6") (pin "K") (pinfunction "CATHODE_K") (pintype "passive"))
      (node (ref "D8") (pin "K") (pinfunction "CATHODE_K") (pintype "passive"))
      (node (ref "Q6") (pin "1") (pinfunction "G_1") (pintype "input"))
      (node (ref "R36") (pin "2") (pinfunction "2_2") (pintype "passive"))
    )
    (net (code "35") (name "Net-(J1-Pad2)") (class "Default")
      (node (ref "J1") (pin "2") (pinfunction "2_2") (pintype "passive"))
      (node (ref "R22") (pin "1") (pinfunction "1_1") (pintype "passive"))
    )
    (net (code "36") (name "Net-(L1-P$2)") (class "Default")
      (node (ref "C26") (pin "+") (pinfunction "+_+") (pintype "passive"))
      (node (ref "C5") (pin "1") (pinfunction "1_1") (pintype "passive"))
      (node (ref "C8") (pin "+") (pinfunction "+_+") (pintype "passive"))
      (node (ref "L1") (pin "2") (pinfunction "P$2_2") (pintype "passive"))
      (node (ref "R1") (pin "2") (pinfunction "2_2") (pintype "passive"))
      (node (ref "U1") (pin "5") (pinfunction "IN-_5") (pintype "bidirectional"))
    )
    (net (code "37") (name "Net-(L2-P$2)") (class "Default")
      (node (ref "C20") (pin "1") (pinfunction "1_1") (pintype "passive"))
      (node (ref "C21") (pin "+") (pinfunction "+_+") (pintype "passive"))
      (node (ref "C22") (pin "+") (pinfunction "+_+") (pintype "passive"))
      (node (ref "L2") (pin "2") (pinfunction "P$2_2") (pintype "passive"))
      (node (ref "R17") (pin "2") (pinfunction "2_2") (pintype "passive"))
      (node (ref "U8") (pin "5") (pinfunction "IN-_5") (pintype "bidirectional"))
    )
    (net (code "38") (name "Net-(LED1-BLUE_A)") (class "Default")
      (node (ref "LED1") (pin "3") (pinfunction "BLUE_A_3") (pintype "bidirectional"))
      (node (ref "R16") (pin "1") (pinfunction "1_1") (pintype "passive"))
    )
    (net (code "39") (name "Net-(LED1-GREEN_A)") (class "Default")
      (node (ref "LED1") (pin "1") (pinfunction "GREEN_A_1") (pintype "bidirectional"))
      (node (ref "R15") (pin "1") (pinfunction "1_1") (pintype "passive"))
    )
    (net (code "40") (name "Net-(LED1-RED_A)") (class "Default")
      (node (ref "LED1") (pin "2") (pinfunction "RED_A_2") (pintype "bidirectional"))
      (node (ref "R14") (pin "1") (pinfunction "1_1") (pintype "passive"))
    )
    (net (code "41") (name "Net-(LED2-BLUE_A)") (class "Default")
      (node (ref "LED2") (pin "3") (pinfunction "BLUE_A_3") (pintype "bidirectional"))
      (node (ref "R35") (pin "1") (pinfunction "1_1") (pintype "passive"))
    )
    (net (code "42") (name "Net-(LED2-GREEN_A)") (class "Default")
      (node (ref "LED2") (pin "1") (pinfunction "GREEN_A_1") (pintype "bidirectional"))
      (node (ref "R34") (pin "1") (pinfunction "1_1") (pintype "passive"))
    )
    (net (code "43") (name "Net-(LED2-RED_A)") (class "Default")
      (node (ref "LED2") (pin "2") (pinfunction "RED_A_2") (pintype "bidirectional"))
      (node (ref "R33") (pin "1") (pinfunction "1_1") (pintype "passive"))
    )
    (net (code "44") (name "Net-(MCU1-PadA8)") (class "Default")
      (node (ref "MCU1") (pin "A8") (pinfunction "A8_A8") (pintype "bidirectional"))
      (node (ref "R2") (pin "2") (pinfunction "2_2") (pintype "passive"))
    )
    (net (code "45") (name "Net-(MCU1-PadA9)") (class "Default")
      (node (ref "MCU1") (pin "A9") (pinfunction "A9_A9") (pintype "bidirectional"))
      (node (ref "R3") (pin "2") (pinfunction "2_2") (pintype "passive"))
    )
    (net (code "46") (name "Net-(MCU1-PadA10)") (class "Default")
      (node (ref "MCU1") (pin "A10") (pinfunction "A10_A10") (pintype "bidirectional"))
      (node (ref "R5") (pin "2") (pinfunction "2_2") (pintype "passive"))
    )
    (net (code "47") (name "Net-(MCU1-PadA11)") (class "Default")
      (node (ref "MCU1") (pin "A11") (pinfunction "A11_A11") (pintype "bidirectional"))
      (node (ref "R6") (pin "2") (pinfunction "2_2") (pintype "passive"))
    )
    (net (code "48") (name "Net-(Q2-G)") (class "Default")
      (node (ref "Q2") (pin "1") (pinfunction "G_1") (pintype "bidirectional"))
      (node (ref "U3") (pin "5") (pinfunction "OUT/N_5") (pintype "bidirectional"))
    )
    (net (code "49") (name "Net-(Q3-G)") (class "Default")
      (node (ref "Q3") (pin "1") (pinfunction "G_1") (pintype "input"))
      (node (ref "R4") (pin "2") (pinfunction "2_2") (pintype "passive"))
      (node (ref "U7") (pin "5") (pinfunction "OUT/N_5") (pintype "bidirectional"))
    )
    (net (code "50") (name "Net-(Q4-G)") (class "Default")
      (node (ref "Q4") (pin "1") (pinfunction "G_1") (pintype "input"))
      (node (ref "R30") (pin "2") (pinfunction "2_2") (pintype "passive"))
      (node (ref "U11") (pin "5") (pinfunction "OUT/N_5") (pintype "bidirectional"))
    )
    (net (code "51") (name "Net-(Q5-G)") (class "Default")
      (node (ref "Q5") (pin "1") (pinfunction "G_1") (pintype "bidirectional"))
      (node (ref "U10") (pin "5") (pinfunction "OUT/N_5") (pintype "bidirectional"))
    )
    (net (code "52") (name "Net-(U1-OUT)") (class "Default")
      (node (ref "R12") (pin "1") (pinfunction "1_1") (pintype "passive"))
      (node (ref "U1") (pin "6") (pinfunction "OUT_6") (pintype "bidirectional"))
    )
    (net (code "53") (name "Net-(U4-VIN+)") (class "Default")
      (node (ref "R18") (pin "2") (pinfunction "2_2") (pintype "passive"))
      (node (ref "R19") (pin "2") (pinfunction "2_2") (pintype "passive"))
      (node (ref "U4") (pin "1") (pinfunction "VIN+_1") (pintype "bidirectional"))
    )
    (net (code "54") (name "Net-(U4-VIN-)") (class "Default")
      (node (ref "R20") (pin "2") (pinfunction "2_2") (pintype "passive"))
      (node (ref "R21") (pin "1") (pinfunction "1_1") (pintype "passive"))
      (node (ref "U4") (pin "3") (pinfunction "VIN-_3") (pintype "bidirectional"))
    )
    (net (code "55") (name "Net-(U8-OUT)") (class "Default")
      (node (ref "R24") (pin "1") (pinfunction "1_1") (pintype "passive"))
      (node (ref "U8") (pin "6") (pinfunction "OUT_6") (pintype "bidirectional"))
    )
    (net (code "56") (name "Net-(U9-VIN+)") (class "Default")
      (node (ref "R26") (pin "2") (pinfunction "2_2") (pintype "passive"))
      (node (ref "R27") (pin "2") (pinfunction "2_2") (pintype "passive"))
      (node (ref "U9") (pin "1") (pinfunction "VIN+_1") (pintype "bidirectional"))
    )
    (net (code "57") (name "Net-(U9-VIN-)") (class "Default")
      (node (ref "R28") (pin "2") (pinfunction "2_2") (pintype "passive"))
      (node (ref "R29") (pin "1") (pinfunction "1_1") (pintype "passive"))
      (node (ref "U9") (pin "3") (pinfunction "VIN-_3") (pintype "bidirectional"))
    )
    (net (code "58") (name "Net-(U12-A0)") (class "Default")
      (node (ref "JP3") (pin "2") (pinfunction "2_2") (pintype "passive"))
      (node (ref "U12") (pin "7") (pinfunction "A0_7") (pintype "bidirectional"))
    )
    (net (code "59") (name "Net-(U12-A1)") (class "Default")
      (node (ref "JP4") (pin "2") (pinfunction "2_2") (pintype "passive"))
      (node (ref "U12") (pin "6") (pinfunction "A1_6") (pintype "bidirectional"))
    )
    (net (code "60") (name "Net-(U12-A2)") (class "Default")
      (node (ref "JP5") (pin "2") (pinfunction "2_2") (pintype "passive"))
      (node (ref "U12") (pin "5") (pinfunction "A2_5") (pintype "bidirectional"))
    )
    (net (code "61") (name "R1") (class "Default")
      (node (ref "MCU1") (pin "B4") (pinfunction "B4_B4") (pintype "bidirectional"))
      (node (ref "R14") (pin "2") (pinfunction "2_2") (pintype "passive"))
    )
    (net (code "62") (name "R2") (class "Default")
      (node (ref "MCU1") (pin "B9") (pinfunction "B9_B9") (pintype "bidirectional"))
      (node (ref "R33") (pin "2") (pinfunction "2_2") (pintype "passive"))
    )
    (net (code "63") (name "RX") (class "Default")
      (node (ref "JP1") (pin "3") (pinfunction "3_3") (pintype "passive"))
      (node (ref "JP2") (pin "1") (pinfunction "1_1") (pintype "passive"))
      (node (ref "MCU1") (pin "B11") (pinfunction "B11_B11") (pintype "bidirectional"))
    )
    (net (code "64") (name "S1") (class "Default")
      (node (ref "MCU1") (pin "B12") (pinfunction "B12_B12") (pintype "bidirectional"))
      (node (ref "S1") (pin "1") (pinfunction "1_1") (pintype "passive"))
      (node (ref "S1") (pin "2") (pinfunction "2_2") (pintype "passive"))
    )
    (net (code "65") (name "S2") (class "Default")
      (node (ref "MCU1") (pin "B13") (pinfunction "B13_B13") (pintype "bidirectional"))
      (node (ref "S2") (pin "1") (pinfunction "1_1") (pintype "passive"))
      (node (ref "S2") (pin "2") (pinfunction "2_2") (pintype "passive"))
    )
    (net (code "66") (name "SCL") (class "Default")
      (node (ref "LCD1") (pin "3=SCL") (pinfunction "SCL_3=SCL") (pintype "bidirectional"))
      (node (ref "MCU1") (pin "B6") (pinfunction "B6_B6") (pintype "bidirectional"))
      (node (ref "U12") (pin "2") (pinfunction "SCL_2") (pintype "bidirectional"))
    )
    (net (code "67") (name "SDA") (class "Default")
      (node (ref "LCD1") (pin "4-SDA") (pinfunction "SDA_4-SDA") (pintype "bidirectional"))
      (node (ref "MCU1") (pin "B7") (pinfunction "B7_B7") (pintype "bidirectional"))
      (node (ref "U12") (pin "1") (pinfunction "SDA_1") (pintype "bidirectional"))
    )
    (net (code "68") (name "TX") (class "Default")
      (node (ref "JP1") (pin "2") (pinfunction "2_2") (pintype "passive"))
      (node (ref "JP2") (pin "2") (pinfunction "2_2") (pintype "passive"))
      (node (ref "MCU1") (pin "B10") (pinfunction "B10_B10") (pintype "bidirectional"))
    )
    (net (code "69") (name "unconnected-(MCU1-PadB14)") (class "Default")
      (node (ref "MCU1") (pin "B14") (pinfunction "B14_B14") (pintype "bidirectional"))
    )
    (net (code "70") (name "unconnected-(MCU1-PadRST)") (class "Default")
      (node (ref "MCU1") (pin "RST") (pinfunction "RST_RST") (pintype "bidirectional"))
    )
    (net (code "71") (name "unconnected-(U12-OS-Pad3)") (class "Default")
      (node (ref "U12") (pin "3") (pinfunction "OS_3") (pintype "bidirectional"))
    )
  )
)
